# Microcontroleur.net
KiCad netlist of a schematic drawn in Altium Designer
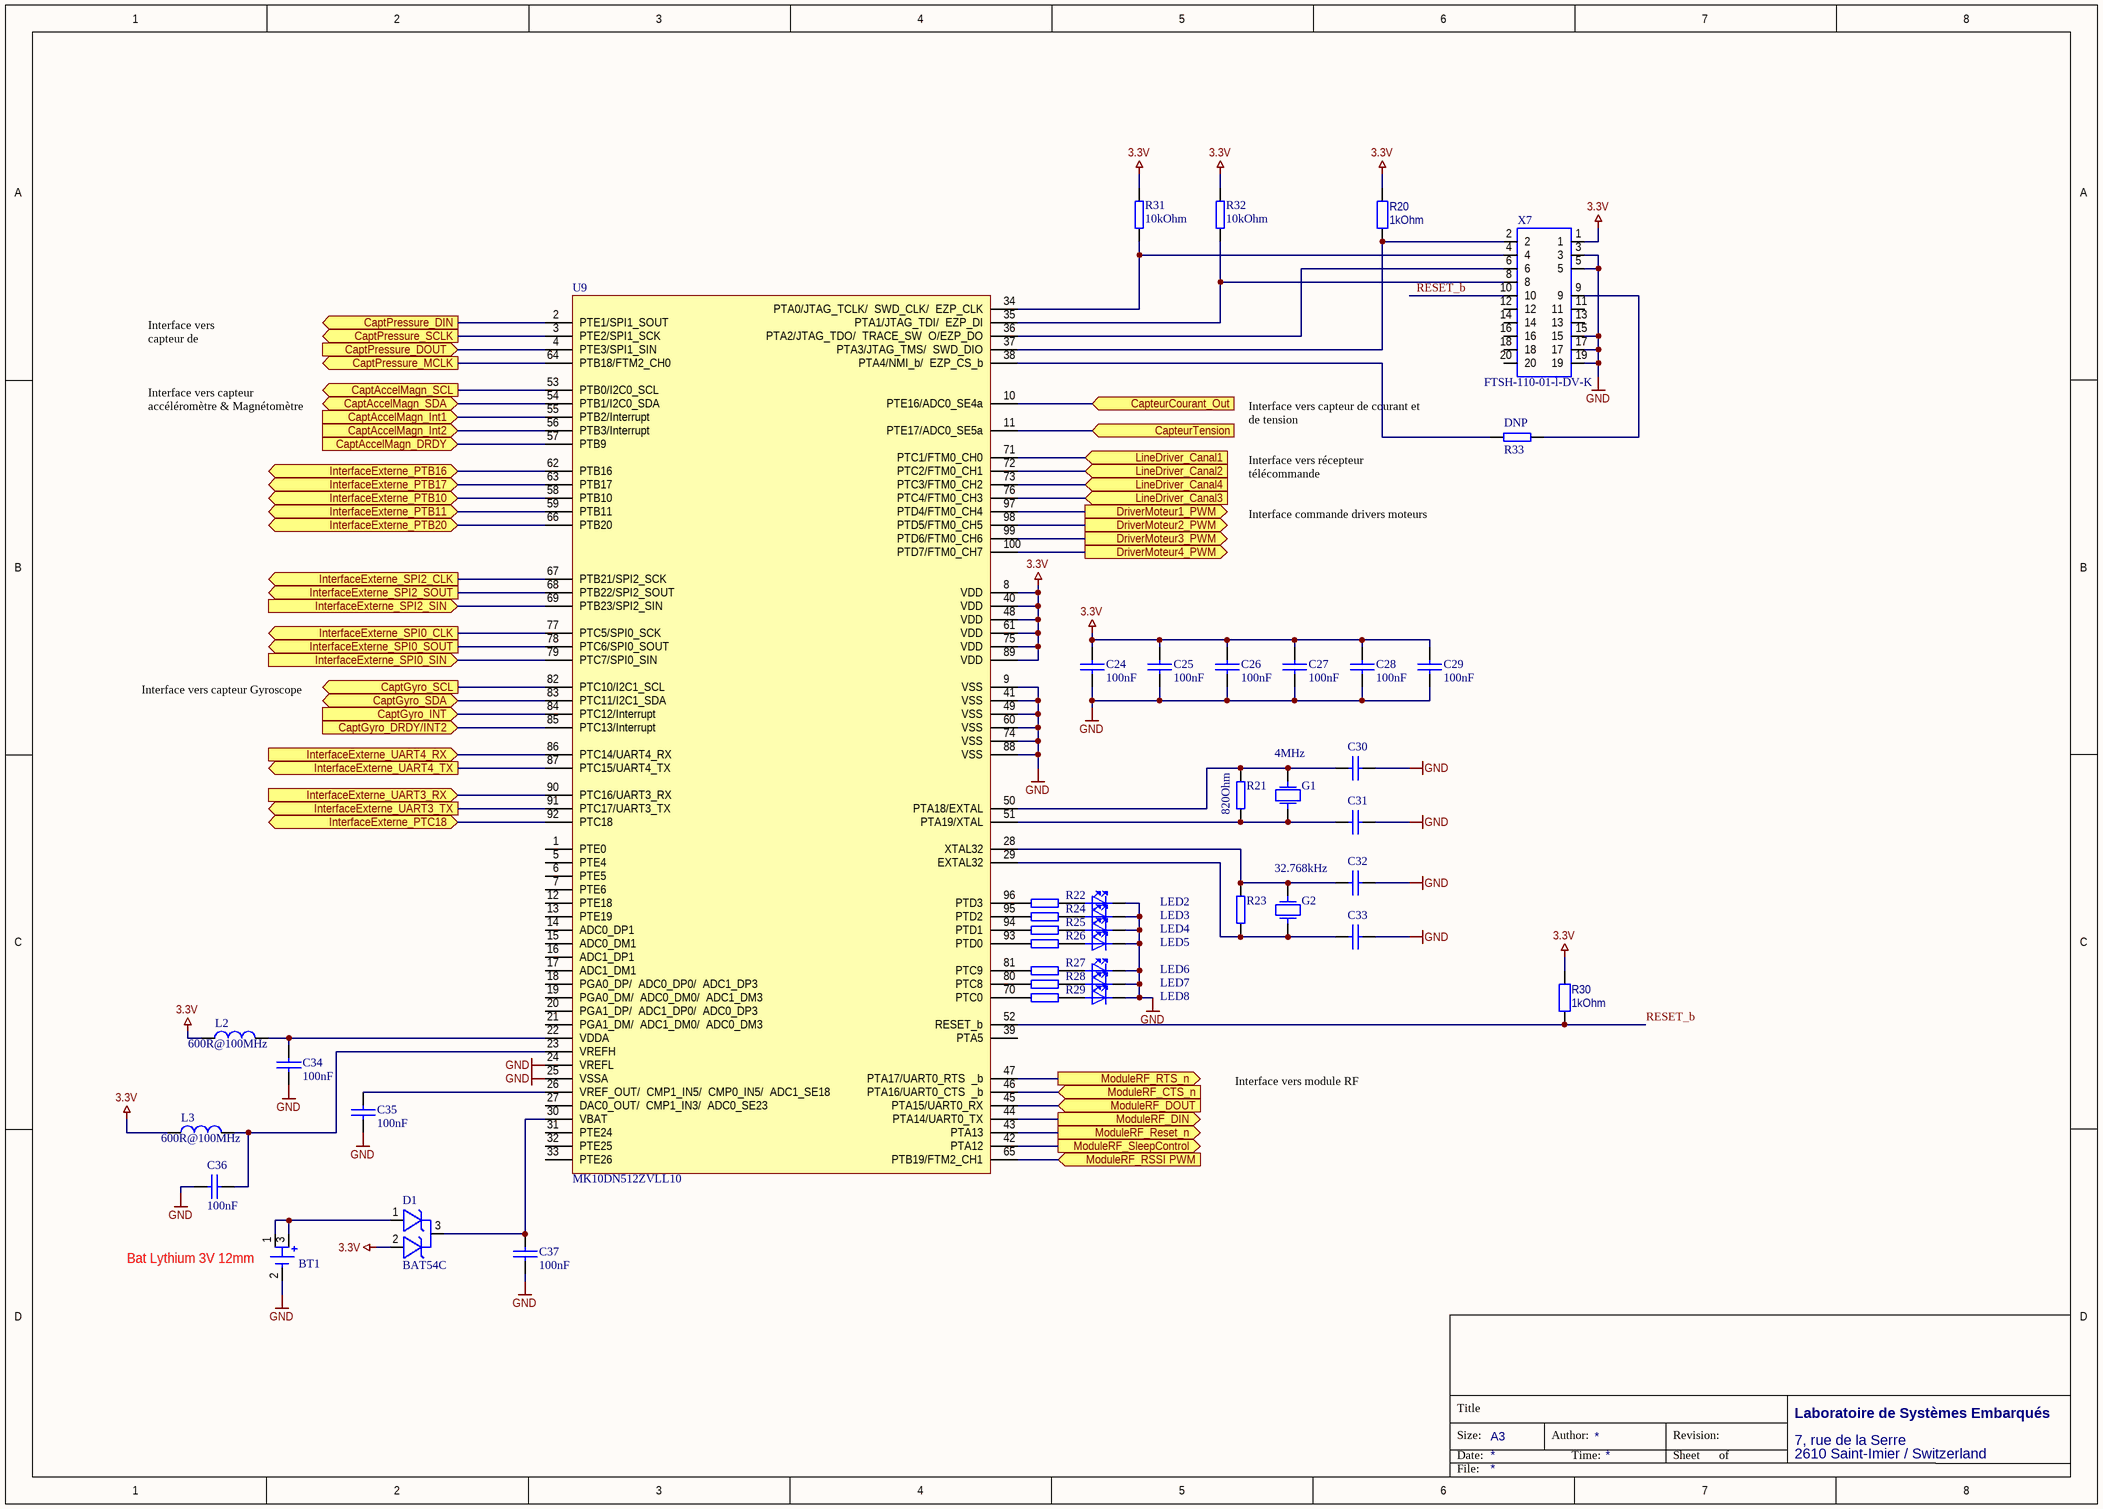
[diagram p0: Microcontroleur.SchDoc]

(export (version "E")
  (design (tool "Eeschema 10.0.6"))
  (components
    (comp (ref "BT1")
      (value "3000TR")
      (footprint "3000TR")
      (description "HOLDER BATTERY COIN 12MM DIA SMD")
      (fields (field (name "MANUFACTURER") "Keystone Electronics"))
      (libsource (lib "EISI") (part "BAT_1"))
    )
    (comp (ref "C24")
      (value "100nF")
      (footprint "060301")
      (description "CAPA")
      (fields (field (name "Comment") "GRM188R71E104KA01D"))
      (libsource (lib "General-Sch-205") (part "CAPA"))
    )
    (comp (ref "C25")
      (value "100nF")
      (footprint "060301")
      (description "CAPA")
      (fields (field (name "Comment") "GRM188R71E104KA01D"))
      (libsource (lib "General-Sch-205") (part "CAPA"))
    )
    (comp (ref "C26")
      (value "100nF")
      (footprint "060301")
      (description "CAPA")
      (fields (field (name "Comment") "GRM188R71E104KA01D"))
      (libsource (lib "General-Sch-205") (part "CAPA"))
    )
    (comp (ref "C27")
      (value "100nF")
      (footprint "060301")
      (description "CAPA")
      (fields (field (name "Comment") "GRM188R71E104KA01D"))
      (libsource (lib "General-Sch-205") (part "CAPA"))
    )
    (comp (ref "C28")
      (value "100nF")
      (footprint "060301")
      (description "CAPA")
      (fields (field (name "Comment") "GRM188R71E104KA01D"))
      (libsource (lib "General-Sch-205") (part "CAPA"))
    )
    (comp (ref "C29")
      (value "100nF")
      (footprint "060301")
      (description "CAPA")
      (fields (field (name "Comment") "GRM188R71E104KA01D"))
      (libsource (lib "General-Sch-205") (part "CAPA"))
    )
    (comp (ref "C30")
      (value "GQM2195C1H200JB01D")
      (footprint "060301")
      (description "CAPA")
      (libsource (lib "General-Sch-205") (part "CAPA"))
    )
    (comp (ref "C31")
      (value "GQM2195C1H200JB01D")
      (footprint "080501")
      (description "CAPA")
      (libsource (lib "General-Sch-205") (part "CAPA"))
    )
    (comp (ref "C32")
      (value "GRM21A5C2E120JW01D")
      (footprint "080501")
      (description "CAPA")
      (libsource (lib "General-Sch-205") (part "CAPA"))
    )
    (comp (ref "C33")
      (value "GRM21A5C2E120JW01D")
      (footprint "080501")
      (description "CAPA")
      (libsource (lib "General-Sch-205") (part "CAPA"))
    )
    (comp (ref "C34")
      (value "100nF")
      (footprint "060301")
      (description "CAPA")
      (fields (field (name "Comment") "GRM188R71E104KA01D"))
      (libsource (lib "General-Sch-205") (part "CAPA"))
    )
    (comp (ref "C35")
      (value "100nF")
      (footprint "060301")
      (description "CAPA")
      (fields (field (name "Comment") "GRM188R71E104KA01D"))
      (libsource (lib "General-Sch-205") (part "CAPA"))
    )
    (comp (ref "C36")
      (value "100nF")
      (footprint "060301")
      (description "CAPA")
      (fields (field (name "Comment") "GRM188R71E104KA01D"))
      (libsource (lib "General-Sch-205") (part "CAPA"))
    )
    (comp (ref "C37")
      (value "100nF")
      (footprint "060301")
      (description "CAPA")
      (fields (field (name "Comment") "GRM188R71E104KA01D"))
      (libsource (lib "General-Sch-205") (part "CAPA"))
    )
    (comp (ref "D1")
      (value "BAT54C")
      (footprint "SOT2301")
      (description "DIODE SCHTTKY CC 200MA 30V SOT23")
      (fields (field (name "MANUFACTURER") "Comchip Technology"))
      (libsource (lib "EISI") (part "BAT54C"))
    )
    (comp (ref "G1")
      (value "4MHz")
      (footprint "Crystal")
      (fields (field (name "Comment") "ECS-40-20-5PX-TR"))
      (libsource (lib "General-Sch-205") (part "CRYSTAL"))
    )
    (comp (ref "G2")
      (value "32.768kHz")
      (footprint "Crystal2")
      (fields (field (name "Comment") "ECS-.327-12.5-38"))
      (libsource (lib "") (part "CRYSTAL_1"))
    )
    (comp (ref "L2")
      (value "600R@100MHz")
      (footprint "080501")
      (description "FERRITE CHIP 600 OHM 200MA 0805")
      (fields (field (name "MANUFACTURER") "Murata Electronics") (field (name "Comment") "BLM21AG601SN1D"))
      (libsource (lib "EISI") (part "Ferrite Bead"))
    )
    (comp (ref "L3")
      (value "600R@100MHz")
      (footprint "080501")
      (description "FERRITE CHIP 600 OHM 200MA 0805")
      (fields (field (name "MANUFACTURER") "Murata Electronics") (field (name "Comment") "BLM21AG601SN1D"))
      (libsource (lib "EISI") (part "Ferrite Bead"))
    )
    (comp (ref "LED2")
      (value "LG L29K-G2J1-24-Z")
      (footprint "060301_led")
      (libsource (lib "Schlib1") (part "LED"))
    )
    (comp (ref "LED3")
      (value "LG L29K-G2J1-24-Z")
      (footprint "060301_led")
      (libsource (lib "Schlib1") (part "LED"))
    )
    (comp (ref "LED4")
      (value "LG L29K-G2J1-24-Z")
      (footprint "060301_led")
      (libsource (lib "Schlib1") (part "LED"))
    )
    (comp (ref "LED5")
      (value "LG L29K-G2J1-24-Z")
      (footprint "060301_led")
      (libsource (lib "Schlib1") (part "LED"))
    )
    (comp (ref "LED6")
      (value "LG L29K-G2J1-24-Z")
      (footprint "060301_led")
      (libsource (lib "Schlib1") (part "LED"))
    )
    (comp (ref "LED7")
      (value "LG L29K-G2J1-24-Z")
      (footprint "060301_led")
      (libsource (lib "Schlib1") (part "LED"))
    )
    (comp (ref "LED8")
      (value "LG L29K-G2J1-24-Z")
      (footprint "060301_led")
      (libsource (lib "Schlib1") (part "LED"))
    )
    (comp (ref "R20")
      (value "1kOhm")
      (footprint "060301")
      (description "RES 1.00K OHM 1/10W 1% 0603 SMD")
      (fields (field (name "MANUFACTURER") "Yageo") (field (name "Comment") "RC0603FR-071KL"))
      (libsource (lib "EISI") (part "RES"))
    )
    (comp (ref "R21")
      (value "820Ohm")
      (footprint "080501")
      (fields (field (name "Comment") "RMCF0805JT820R"))
      (libsource (lib "General-Sch-205") (part "RES"))
    )
    (comp (ref "R22")
      (value "RMCF0805JT820R")
      (footprint "080501")
      (libsource (lib "General-Sch-205") (part "RES"))
    )
    (comp (ref "R23")
      (value "ERJ-6GEYJ103V")
      (footprint "080501")
      (libsource (lib "General-Sch-205") (part "RES"))
    )
    (comp (ref "R24")
      (value "RMCF0805JT820R")
      (footprint "080501")
      (libsource (lib "General-Sch-205") (part "RES"))
    )
    (comp (ref "R25")
      (value "RMCF0805JT820R")
      (footprint "080501")
      (libsource (lib "General-Sch-205") (part "RES"))
    )
    (comp (ref "R26")
      (value "RMCF0805JT820R")
      (footprint "080501")
      (libsource (lib "General-Sch-205") (part "RES"))
    )
    (comp (ref "R27")
      (value "RMCF0805JT820R")
      (footprint "080501")
      (libsource (lib "General-Sch-205") (part "RES"))
    )
    (comp (ref "R28")
      (value "RMCF0805JT820R")
      (footprint "080501")
      (libsource (lib "General-Sch-205") (part "RES"))
    )
    (comp (ref "R29")
      (value "RMCF0805JT820R")
      (footprint "080501")
      (libsource (lib "General-Sch-205") (part "RES"))
    )
    (comp (ref "R30")
      (value "1kOhm")
      (footprint "060301")
      (description "RES 1.00K OHM 1/10W 1% 0603 SMD")
      (fields (field (name "MANUFACTURER") "Yageo") (field (name "Comment") "RC0603FR-071KL"))
      (libsource (lib "EISI") (part "RES"))
    )
    (comp (ref "R31")
      (value "10kOhm")
      (footprint "080501")
      (fields (field (name "Comment") "ERJ-6GEYJ103V"))
      (libsource (lib "General-Sch-205") (part "RES"))
    )
    (comp (ref "R32")
      (value "10kOhm")
      (footprint "080501")
      (fields (field (name "Comment") "ERJ-6GEYJ103V"))
      (libsource (lib "General-Sch-205") (part "RES"))
    )
    (comp (ref "R33")
      (value "DNP")
      (footprint "080501")
      (fields (field (name "Comment") "RMCF0805JT820R"))
      (libsource (lib "General-Sch-205") (part "RES"))
    )
    (comp (ref "U9")
      (value "MK10DN512ZVLL10")
      (footprint "QFP100-1")
      (libsource (lib "Schlib1") (part "MK10DN512ZVLL10"))
    )
    (comp (ref "X7")
      (value "FTSH-110-01-l-DV-K")
      (footprint "FTSH-110-01-X-DV-EJ")
      (description "CONN UNSHROUDED HDR 20POS .05\"")
      (fields (field (name "MANUFACTURER") "Samtec Inc"))
      (libsource (lib "EISI") (part "CON20_JTAG"))
    )
  )
  (nets
    (net (code "1") (name "/CaptAccelMagn_DRDY") (class "Default")
      (node (ref "U9") (pin "57") (pinfunction "PTB9_57") (pintype "passive"))
    )
    (net (code "2") (name "/CaptAccelMagn_Int1") (class "Default")
      (node (ref "U9") (pin "55") (pinfunction "PTB2/Interrupt_55") (pintype "passive"))
    )
    (net (code "3") (name "/CaptAccelMagn_Int2") (class "Default")
      (node (ref "U9") (pin "56") (pinfunction "PTB3/Interrupt_56") (pintype "passive"))
    )
    (net (code "4") (name "/CaptAccelMagn_SCL") (class "Default")
      (node (ref "U9") (pin "53") (pinfunction "PTB0/I2C0_SCL_53") (pintype "passive"))
    )
    (net (code "5") (name "/CaptAccelMagn_SDA") (class "Default")
      (node (ref "U9") (pin "54") (pinfunction "PTB1/I2C0_SDA_54") (pintype "passive"))
    )
    (net (code "6") (name "/CaptGyro_DRDY{slash}INT2") (class "Default")
      (node (ref "U9") (pin "85") (pinfunction "PTC13/Interrupt_85") (pintype "passive"))
    )
    (net (code "7") (name "/CaptGyro_INT") (class "Default")
      (node (ref "U9") (pin "84") (pinfunction "PTC12/Interrupt_84") (pintype "passive"))
    )
    (net (code "8") (name "/CaptGyro_SCL") (class "Default")
      (node (ref "U9") (pin "82") (pinfunction "PTC10/I2C1_SCL_82") (pintype "passive"))
    )
    (net (code "9") (name "/CaptGyro_SDA") (class "Default")
      (node (ref "U9") (pin "83") (pinfunction "PTC11/I2C1_SDA_83") (pintype "passive"))
    )
    (net (code "10") (name "/CaptPressure_DIN") (class "Default")
      (node (ref "U9") (pin "2") (pinfunction "PTE1/SPI1_SOUT_2") (pintype "passive"))
    )
    (net (code "11") (name "/CaptPressure_DOUT") (class "Default")
      (node (ref "U9") (pin "4") (pinfunction "PTE3/SPI1_SIN_4") (pintype "passive"))
    )
    (net (code "12") (name "/CaptPressure_MCLK") (class "Default")
      (node (ref "U9") (pin "64") (pinfunction "PTB18/FTM2_CH0_64") (pintype "passive"))
    )
    (net (code "13") (name "/CaptPressure_SCLK") (class "Default")
      (node (ref "U9") (pin "3") (pinfunction "PTE2/SPI1_SCK_3") (pintype "passive"))
    )
    (net (code "14") (name "/CapteurCourant_Out") (class "Default")
      (node (ref "U9") (pin "10") (pinfunction "PTE16/ADC0_SE4a_10") (pintype "passive"))
    )
    (net (code "15") (name "/CapteurTension") (class "Default")
      (node (ref "U9") (pin "11") (pinfunction "PTE17/ADC0_SE5a_11") (pintype "passive"))
    )
    (net (code "16") (name "/DriverMoteur1_PWM") (class "Default")
      (node (ref "U9") (pin "97") (pinfunction "PTD4/FTM0_CH4_97") (pintype "passive"))
    )
    (net (code "17") (name "/DriverMoteur2_PWM") (class "Default")
      (node (ref "U9") (pin "98") (pinfunction "PTD5/FTM0_CH5_98") (pintype "passive"))
    )
    (net (code "18") (name "/DriverMoteur3_PWM") (class "Default")
      (node (ref "U9") (pin "99") (pinfunction "PTD6/FTM0_CH6_99") (pintype "passive"))
    )
    (net (code "19") (name "/DriverMoteur4_PWM") (class "Default")
      (node (ref "U9") (pin "100") (pinfunction "PTD7/FTM0_CH7_100") (pintype "passive"))
    )
    (net (code "20") (name "/InterfaceExterne_PTB10") (class "Default")
      (node (ref "U9") (pin "58") (pinfunction "PTB10_58") (pintype "passive"))
    )
    (net (code "21") (name "/InterfaceExterne_PTB11") (class "Default")
      (node (ref "U9") (pin "59") (pinfunction "PTB11_59") (pintype "passive"))
    )
    (net (code "22") (name "/InterfaceExterne_PTB16") (class "Default")
      (node (ref "U9") (pin "62") (pinfunction "PTB16_62") (pintype "passive"))
    )
    (net (code "23") (name "/InterfaceExterne_PTB17") (class "Default")
      (node (ref "U9") (pin "63") (pinfunction "PTB17_63") (pintype "passive"))
    )
    (net (code "24") (name "/InterfaceExterne_PTB20") (class "Default")
      (node (ref "U9") (pin "66") (pinfunction "PTB20_66") (pintype "passive"))
    )
    (net (code "25") (name "/InterfaceExterne_PTC18") (class "Default")
      (node (ref "U9") (pin "92") (pinfunction "PTC18_92") (pintype "passive"))
    )
    (net (code "26") (name "/InterfaceExterne_SPI0_CLK") (class "Default")
      (node (ref "U9") (pin "77") (pinfunction "PTC5/SPI0_SCK_77") (pintype "passive"))
    )
    (net (code "27") (name "/InterfaceExterne_SPI0_SIN") (class "Default")
      (node (ref "U9") (pin "79") (pinfunction "PTC7/SPI0_SIN_79") (pintype "passive"))
    )
    (net (code "28") (name "/InterfaceExterne_SPI0_SOUT") (class "Default")
      (node (ref "U9") (pin "78") (pinfunction "PTC6/SPI0_SOUT_78") (pintype "passive"))
    )
    (net (code "29") (name "/InterfaceExterne_SPI2_CLK") (class "Default")
      (node (ref "U9") (pin "67") (pinfunction "PTB21/SPI2_SCK_67") (pintype "passive"))
    )
    (net (code "30") (name "/InterfaceExterne_SPI2_SIN") (class "Default")
      (node (ref "U9") (pin "69") (pinfunction "PTB23/SPI2_SIN_69") (pintype "passive"))
    )
    (net (code "31") (name "/InterfaceExterne_SPI2_SOUT") (class "Default")
      (node (ref "U9") (pin "68") (pinfunction "PTB22/SPI2_SOUT_68") (pintype "passive"))
    )
    (net (code "32") (name "/InterfaceExterne_UART3_RX") (class "Default")
      (node (ref "U9") (pin "90") (pinfunction "PTC16/UART3_RX_90") (pintype "passive"))
    )
    (net (code "33") (name "/InterfaceExterne_UART3_TX") (class "Default")
      (node (ref "U9") (pin "91") (pinfunction "PTC17/UART3_TX_91") (pintype "passive"))
    )
    (net (code "34") (name "/InterfaceExterne_UART4_RX") (class "Default")
      (node (ref "U9") (pin "86") (pinfunction "PTC14/UART4_RX_86") (pintype "passive"))
    )
    (net (code "35") (name "/InterfaceExterne_UART4_TX") (class "Default")
      (node (ref "U9") (pin "87") (pinfunction "PTC15/UART4_TX_87") (pintype "passive"))
    )
    (net (code "36") (name "/LineDriver_Canal1") (class "Default")
      (node (ref "U9") (pin "71") (pinfunction "PTC1/FTM0_CH0_71") (pintype "passive"))
    )
    (net (code "37") (name "/LineDriver_Canal2") (class "Default")
      (node (ref "U9") (pin "72") (pinfunction "PTC2/FTM0_CH1_72") (pintype "passive"))
    )
    (net (code "38") (name "/LineDriver_Canal3") (class "Default")
      (node (ref "U9") (pin "76") (pinfunction "PTC4/FTM0_CH3_76") (pintype "passive"))
    )
    (net (code "39") (name "/LineDriver_Canal4") (class "Default")
      (node (ref "U9") (pin "73") (pinfunction "PTC3/FTM0_CH2_73") (pintype "passive"))
    )
    (net (code "40") (name "/ModuleRF_CTS_n") (class "Default")
      (node (ref "U9") (pin "46") (pinfunction "PTA16/UART0_CTS___b_46") (pintype "passive"))
    )
    (net (code "41") (name "/ModuleRF_DIN") (class "Default")
      (node (ref "U9") (pin "44") (pinfunction "PTA14/UART0_TX_44") (pintype "passive"))
    )
    (net (code "42") (name "/ModuleRF_DOUT") (class "Default")
      (node (ref "U9") (pin "45") (pinfunction "PTA15/UART0_RX_45") (pintype "passive"))
    )
    (net (code "43") (name "/ModuleRF_RSSI PWM") (class "Default")
      (node (ref "U9") (pin "65") (pinfunction "PTB19/FTM2_CH1_65") (pintype "passive"))
    )
    (net (code "44") (name "/ModuleRF_RTS_n") (class "Default")
      (node (ref "U9") (pin "47") (pinfunction "PTA17/UART0_RTS___b_47") (pintype "passive"))
    )
    (net (code "45") (name "/ModuleRF_Reset_n") (class "Default")
      (node (ref "U9") (pin "43") (pinfunction "PTA13_43") (pintype "passive"))
    )
    (net (code "46") (name "/ModuleRF_SleepControl") (class "Default")
      (node (ref "U9") (pin "42") (pinfunction "PTA12_42") (pintype "passive"))
    )
    (net (code "47") (name "/RESET_b") (class "Default")
      (node (ref "R30") (pin "2") (pinfunction "2_2") (pintype "passive"))
      (node (ref "U9") (pin "52") (pinfunction "RESET_b_52") (pintype "passive"))
      (node (ref "X7") (pin "10") (pinfunction "10_10") (pintype "passive"))
    )
    (net (code "48") (name "3.3V") (class "Default")
      (node (ref "C24") (pin "1") (pintype "passive"))
      (node (ref "C25") (pin "1") (pintype "passive"))
      (node (ref "C26") (pin "1") (pintype "passive"))
      (node (ref "C27") (pin "1") (pintype "passive"))
      (node (ref "C28") (pin "1") (pintype "passive"))
      (node (ref "C29") (pin "1") (pintype "passive"))
      (node (ref "D1") (pin "2") (pinfunction "C2_2") (pintype "passive"))
      (node (ref "L2") (pin "1") (pinfunction "1_1") (pintype "passive"))
      (node (ref "L3") (pin "1") (pinfunction "1_1") (pintype "passive"))
      (node (ref "R20") (pin "1") (pinfunction "1_1") (pintype "passive"))
      (node (ref "R30") (pin "1") (pinfunction "1_1") (pintype "passive"))
      (node (ref "R31") (pin "2") (pintype "passive"))
      (node (ref "R32") (pin "2") (pintype "passive"))
      (node (ref "U9") (pin "40") (pinfunction "VDD_40") (pintype "passive"))
      (node (ref "U9") (pin "48") (pinfunction "VDD_48") (pintype "passive"))
      (node (ref "U9") (pin "61") (pinfunction "VDD_61") (pintype "passive"))
      (node (ref "U9") (pin "75") (pinfunction "VDD_75") (pintype "passive"))
      (node (ref "U9") (pin "8") (pinfunction "VDD_8") (pintype "passive"))
      (node (ref "U9") (pin "89") (pinfunction "VDD_89") (pintype "passive"))
      (node (ref "X7") (pin "1") (pinfunction "1_1") (pintype "passive"))
    )
    (net (code "49") (name "GND") (class "Default")
      (node (ref "BT1") (pin "2") (pinfunction "C_2") (pintype "passive"))
      (node (ref "C24") (pin "2") (pintype "passive"))
      (node (ref "C25") (pin "2") (pintype "passive"))
      (node (ref "C26") (pin "2") (pintype "passive"))
      (node (ref "C27") (pin "2") (pintype "passive"))
      (node (ref "C28") (pin "2") (pintype "passive"))
      (node (ref "C29") (pin "2") (pintype "passive"))
      (node (ref "C30") (pin "2") (pintype "passive"))
      (node (ref "C31") (pin "2") (pintype "passive"))
      (node (ref "C32") (pin "2") (pintype "passive"))
      (node (ref "C33") (pin "2") (pintype "passive"))
      (node (ref "C34") (pin "2") (pintype "passive"))
      (node (ref "C35") (pin "1") (pintype "passive"))
      (node (ref "C36") (pin "1") (pintype "passive"))
      (node (ref "C37") (pin "1") (pintype "passive"))
      (node (ref "LED2") (pin "2") (pinfunction "CATHODE_2") (pintype "passive"))
      (node (ref "LED3") (pin "2") (pinfunction "CATHODE_2") (pintype "passive"))
      (node (ref "LED4") (pin "2") (pinfunction "CATHODE_2") (pintype "passive"))
      (node (ref "LED5") (pin "2") (pinfunction "CATHODE_2") (pintype "passive"))
      (node (ref "LED6") (pin "2") (pinfunction "CATHODE_2") (pintype "passive"))
      (node (ref "LED7") (pin "2") (pinfunction "CATHODE_2") (pintype "passive"))
      (node (ref "LED8") (pin "2") (pinfunction "CATHODE_2") (pintype "passive"))
      (node (ref "U9") (pin "24") (pinfunction "VREFL_24") (pintype "passive"))
      (node (ref "U9") (pin "25") (pinfunction "VSSA_25") (pintype "passive"))
      (node (ref "U9") (pin "41") (pinfunction "VSS_41") (pintype "passive"))
      (node (ref "U9") (pin "49") (pinfunction "VSS_49") (pintype "passive"))
      (node (ref "U9") (pin "60") (pinfunction "VSS_60") (pintype "passive"))
      (node (ref "U9") (pin "74") (pinfunction "VSS_74") (pintype "passive"))
      (node (ref "U9") (pin "88") (pinfunction "VSS_88") (pintype "passive"))
      (node (ref "U9") (pin "9") (pinfunction "VSS_9") (pintype "passive"))
      (node (ref "X7") (pin "15") (pinfunction "15_15") (pintype "passive"))
      (node (ref "X7") (pin "17") (pinfunction "17_17") (pintype "passive"))
      (node (ref "X7") (pin "19") (pinfunction "19_19") (pintype "passive"))
      (node (ref "X7") (pin "3") (pinfunction "3_3") (pintype "passive"))
      (node (ref "X7") (pin "5") (pinfunction "5_5") (pintype "passive"))
    )
    (net (code "50") (name "Net-(BT1-A1)") (class "Default")
      (node (ref "BT1") (pin "1") (pinfunction "A1_1") (pintype "passive"))
      (node (ref "BT1") (pin "3") (pinfunction "A2_3") (pintype "passive"))
      (node (ref "D1") (pin "1") (pinfunction "C1_1") (pintype "passive"))
    )
    (net (code "51") (name "Net-(D1-Anode)") (class "Default")
      (node (ref "C37") (pin "2") (pintype "passive"))
      (node (ref "D1") (pin "3") (pinfunction "Anode_3") (pintype "passive"))
      (node (ref "U9") (pin "30") (pinfunction "VBAT_30") (pintype "passive"))
    )
    (net (code "52") (name "Net-(LED2-ANODE)") (class "Default")
      (node (ref "LED2") (pin "1") (pinfunction "ANODE_1") (pintype "passive"))
      (node (ref "R24") (pin "2") (pintype "passive"))
    )
    (net (code "53") (name "Net-(LED3-ANODE)") (class "Default")
      (node (ref "LED3") (pin "1") (pinfunction "ANODE_1") (pintype "passive"))
      (node (ref "R22") (pin "2") (pintype "passive"))
    )
    (net (code "54") (name "Net-(LED4-ANODE)") (class "Default")
      (node (ref "LED4") (pin "1") (pinfunction "ANODE_1") (pintype "passive"))
      (node (ref "R25") (pin "2") (pintype "passive"))
    )
    (net (code "55") (name "Net-(LED5-ANODE)") (class "Default")
      (node (ref "LED5") (pin "1") (pinfunction "ANODE_1") (pintype "passive"))
      (node (ref "R26") (pin "2") (pintype "passive"))
    )
    (net (code "56") (name "Net-(LED6-ANODE)") (class "Default")
      (node (ref "LED6") (pin "1") (pinfunction "ANODE_1") (pintype "passive"))
      (node (ref "R27") (pin "2") (pintype "passive"))
    )
    (net (code "57") (name "Net-(LED7-ANODE)") (class "Default")
      (node (ref "LED7") (pin "1") (pinfunction "ANODE_1") (pintype "passive"))
      (node (ref "R28") (pin "2") (pintype "passive"))
    )
    (net (code "58") (name "Net-(LED8-ANODE)") (class "Default")
      (node (ref "LED8") (pin "1") (pinfunction "ANODE_1") (pintype "passive"))
      (node (ref "R29") (pin "2") (pintype "passive"))
    )
    (net (code "59") (name "Net-(R33-Pad1)") (class "Default")
      (node (ref "R33") (pin "1") (pintype "passive"))
      (node (ref "X7") (pin "9") (pinfunction "9_9") (pintype "passive"))
    )
    (net (code "60") (name "Net-(U9-EXTAL32)") (class "Default")
      (node (ref "C33") (pin "1") (pintype "passive"))
      (node (ref "G2") (pin "1") (pintype "passive"))
      (node (ref "R23") (pin "1") (pintype "passive"))
      (node (ref "U9") (pin "29") (pinfunction "EXTAL32_29") (pintype "passive"))
    )
    (net (code "61") (name "Net-(U9-PTA0{slash}JTAG_TCLK{slash}__SWD_CLK{slash}__EZP_CLK)") (class "Default")
      (node (ref "R31") (pin "1") (pintype "passive"))
      (node (ref "U9") (pin "34") (pinfunction "PTA0/JTAG_TCLK/__SWD_CLK/__EZP_CLK_34") (pintype "passive"))
      (node (ref "X7") (pin "4") (pinfunction "4_4") (pintype "passive"))
    )
    (net (code "62") (name "Net-(U9-PTA1{slash}JTAG_TDI{slash}__EZP_DI)") (class "Default")
      (node (ref "R32") (pin "1") (pintype "passive"))
      (node (ref "U9") (pin "35") (pinfunction "PTA1/JTAG_TDI/__EZP_DI_35") (pintype "passive"))
      (node (ref "X7") (pin "8") (pinfunction "8_8") (pintype "passive"))
    )
    (net (code "63") (name "Net-(U9-PTA2{slash}JTAG_TDO{slash}__TRACE_SW__O{slash}EZP_DO)") (class "Default")
      (node (ref "U9") (pin "36") (pinfunction "PTA2/JTAG_TDO/__TRACE_SW__O/EZP_DO_36") (pintype "passive"))
      (node (ref "X7") (pin "6") (pinfunction "6_6") (pintype "passive"))
    )
    (net (code "64") (name "Net-(U9-PTA3{slash}JTAG_TMS{slash}__SWD_DIO)") (class "Default")
      (node (ref "R20") (pin "2") (pinfunction "2_2") (pintype "passive"))
      (node (ref "U9") (pin "37") (pinfunction "PTA3/JTAG_TMS/__SWD_DIO_37") (pintype "passive"))
      (node (ref "X7") (pin "2") (pinfunction "2_2") (pintype "passive"))
    )
    (net (code "65") (name "Net-(U9-PTA4{slash}NMI_b{slash}__EZP_CS_b)") (class "Default")
      (node (ref "R33") (pin "2") (pintype "passive"))
      (node (ref "U9") (pin "38") (pinfunction "PTA4/NMI_b/__EZP_CS_b_38") (pintype "passive"))
    )
    (net (code "66") (name "Net-(U9-PTA18{slash}EXTAL)") (class "Default")
      (node (ref "C30") (pin "1") (pintype "passive"))
      (node (ref "G1") (pin "1") (pintype "passive"))
      (node (ref "R21") (pin "2") (pintype "passive"))
      (node (ref "U9") (pin "50") (pinfunction "PTA18/EXTAL_50") (pintype "passive"))
    )
    (net (code "67") (name "Net-(U9-PTA19{slash}XTAL)") (class "Default")
      (node (ref "C31") (pin "1") (pintype "passive"))
      (node (ref "G1") (pin "2") (pinfunction "2_2") (pintype "passive"))
      (node (ref "R21") (pin "1") (pintype "passive"))
      (node (ref "U9") (pin "51") (pinfunction "PTA19/XTAL_51") (pintype "passive"))
    )
    (net (code "68") (name "Net-(U9-PTC0)") (class "Default")
      (node (ref "R29") (pin "1") (pintype "passive"))
      (node (ref "U9") (pin "70") (pinfunction "PTC0_70") (pintype "passive"))
    )
    (net (code "69") (name "Net-(U9-PTC8)") (class "Default")
      (node (ref "R28") (pin "1") (pintype "passive"))
      (node (ref "U9") (pin "80") (pinfunction "PTC8_80") (pintype "passive"))
    )
    (net (code "70") (name "Net-(U9-PTC9)") (class "Default")
      (node (ref "R27") (pin "1") (pintype "passive"))
      (node (ref "U9") (pin "81") (pinfunction "PTC9_81") (pintype "passive"))
    )
    (net (code "71") (name "Net-(U9-PTD0)") (class "Default")
      (node (ref "R26") (pin "1") (pintype "passive"))
      (node (ref "U9") (pin "93") (pinfunction "PTD0_93") (pintype "passive"))
    )
    (net (code "72") (name "Net-(U9-PTD1)") (class "Default")
      (node (ref "R25") (pin "1") (pintype "passive"))
      (node (ref "U9") (pin "94") (pinfunction "PTD1_94") (pintype "passive"))
    )
    (net (code "73") (name "Net-(U9-PTD2)") (class "Default")
      (node (ref "R24") (pin "1") (pintype "passive"))
      (node (ref "U9") (pin "95") (pinfunction "PTD2_95") (pintype "passive"))
    )
    (net (code "74") (name "Net-(U9-PTD3)") (class "Default")
      (node (ref "R22") (pin "1") (pintype "passive"))
      (node (ref "U9") (pin "96") (pinfunction "PTD3_96") (pintype "passive"))
    )
    (net (code "75") (name "Net-(U9-VDDA)") (class "Default")
      (node (ref "C34") (pin "1") (pintype "passive"))
      (node (ref "L2") (pin "2") (pinfunction "2_2") (pintype "passive"))
      (node (ref "U9") (pin "22") (pinfunction "VDDA_22") (pintype "passive"))
    )
    (net (code "76") (name "Net-(U9-VREFH)") (class "Default")
      (node (ref "C36") (pin "2") (pintype "passive"))
      (node (ref "L3") (pin "2") (pinfunction "2_2") (pintype "passive"))
      (node (ref "U9") (pin "23") (pinfunction "VREFH_23") (pintype "passive"))
    )
    (net (code "77") (name "Net-(U9-VREF_OUT{slash}__CMP1_IN5{slash}__CMP0_IN5{slash}__ADC1_SE18)") (class "Default")
      (node (ref "C35") (pin "2") (pintype "passive"))
      (node (ref "U9") (pin "26") (pinfunction "VREF_OUT/__CMP1_IN5/__CMP0_IN5/__ADC1_SE18_26") (pintype "passive"))
    )
    (net (code "78") (name "Net-(U9-XTAL32)") (class "Default")
      (node (ref "C32") (pin "1") (pintype "passive"))
      (node (ref "G2") (pin "2") (pintype "passive"))
      (node (ref "R23") (pin "2") (pintype "passive"))
      (node (ref "U9") (pin "28") (pinfunction "XTAL32_28") (pintype "passive"))
    )
    (net (code "79") (name "unconnected-(U9-ADC0_DM1-Pad15)") (class "Default")
      (node (ref "U9") (pin "15") (pinfunction "ADC0_DM1_15") (pintype "passive"))
    )
    (net (code "80") (name "unconnected-(U9-ADC0_DP1-Pad14)") (class "Default")
      (node (ref "U9") (pin "14") (pinfunction "ADC0_DP1_14") (pintype "passive"))
    )
    (net (code "81") (name "unconnected-(U9-ADC1_DM1-Pad17)") (class "Default")
      (node (ref "U9") (pin "17") (pinfunction "ADC1_DM1_17") (pintype "passive"))
    )
    (net (code "82") (name "unconnected-(U9-ADC1_DP1-Pad16)") (class "Default")
      (node (ref "U9") (pin "16") (pinfunction "ADC1_DP1_16") (pintype "passive"))
    )
    (net (code "83") (name "unconnected-(U9-DAC0_OUT{slash}__CMP1_IN3{slash}__ADC0_SE23-Pad27)") (class "Default")
      (node (ref "U9") (pin "27") (pinfunction "DAC0_OUT/__CMP1_IN3/__ADC0_SE23_27") (pintype "passive"))
    )
    (net (code "84") (name "unconnected-(U9-PGA0_DM{slash}__ADC0_DM0{slash}__ADC1_DM3-Pad19)") (class "Default")
      (node (ref "U9") (pin "19") (pinfunction "PGA0_DM/__ADC0_DM0/__ADC1_DM3_19") (pintype "passive"))
    )
    (net (code "85") (name "unconnected-(U9-PGA0_DP{slash}__ADC0_DP0{slash}__ADC1_DP3-Pad18)") (class "Default")
      (node (ref "U9") (pin "18") (pinfunction "PGA0_DP/__ADC0_DP0/__ADC1_DP3_18") (pintype "passive"))
    )
    (net (code "86") (name "unconnected-(U9-PGA1_DM{slash}__ADC1_DM0{slash}__ADC0_DM3-Pad21)") (class "Default")
      (node (ref "U9") (pin "21") (pinfunction "PGA1_DM/__ADC1_DM0/__ADC0_DM3_21") (pintype "passive"))
    )
    (net (code "87") (name "unconnected-(U9-PGA1_DP{slash}__ADC1_DP0{slash}__ADC0_DP3-Pad20)") (class "Default")
      (node (ref "U9") (pin "20") (pinfunction "PGA1_DP/__ADC1_DP0/__ADC0_DP3_20") (pintype "passive"))
    )
    (net (code "88") (name "unconnected-(U9-PTA5-Pad39)") (class "Default")
      (node (ref "U9") (pin "39") (pinfunction "PTA5_39") (pintype "passive"))
    )
    (net (code "89") (name "unconnected-(U9-PTE0-Pad1)") (class "Default")
      (node (ref "U9") (pin "1") (pinfunction "PTE0_1") (pintype "passive"))
    )
    (net (code "90") (name "unconnected-(U9-PTE4-Pad5)") (class "Default")
      (node (ref "U9") (pin "5") (pinfunction "PTE4_5") (pintype "passive"))
    )
    (net (code "91") (name "unconnected-(U9-PTE5-Pad6)") (class "Default")
      (node (ref "U9") (pin "6") (pinfunction "PTE5_6") (pintype "passive"))
    )
    (net (code "92") (name "unconnected-(U9-PTE6-Pad7)") (class "Default")
      (node (ref "U9") (pin "7") (pinfunction "PTE6_7") (pintype "passive"))
    )
    (net (code "93") (name "unconnected-(U9-PTE18-Pad12)") (class "Default")
      (node (ref "U9") (pin "12") (pinfunction "PTE18_12") (pintype "passive"))
    )
    (net (code "94") (name "unconnected-(U9-PTE19-Pad13)") (class "Default")
      (node (ref "U9") (pin "13") (pinfunction "PTE19_13") (pintype "passive"))
    )
    (net (code "95") (name "unconnected-(U9-PTE24-Pad31)") (class "Default")
      (node (ref "U9") (pin "31") (pinfunction "PTE24_31") (pintype "passive"))
    )
    (net (code "96") (name "unconnected-(U9-PTE25-Pad32)") (class "Default")
      (node (ref "U9") (pin "32") (pinfunction "PTE25_32") (pintype "passive"))
    )
    (net (code "97") (name "unconnected-(U9-PTE26-Pad33)") (class "Default")
      (node (ref "U9") (pin "33") (pinfunction "PTE26_33") (pintype "passive"))
    )
    (net (code "98") (name "unconnected-(X7-Pad11)") (class "Default")
      (node (ref "X7") (pin "11") (pinfunction "11_11") (pintype "passive"))
    )
    (net (code "99") (name "unconnected-(X7-Pad12)") (class "Default")
      (node (ref "X7") (pin "12") (pinfunction "12_12") (pintype "passive"))
    )
    (net (code "100") (name "unconnected-(X7-Pad13)") (class "Default")
      (node (ref "X7") (pin "13") (pinfunction "13_13") (pintype "passive"))
    )
    (net (code "101") (name "unconnected-(X7-Pad14)") (class "Default")
      (node (ref "X7") (pin "14") (pinfunction "14_14") (pintype "passive"))
    )
    (net (code "102") (name "unconnected-(X7-Pad16)") (class "Default")
      (node (ref "X7") (pin "16") (pinfunction "16_16") (pintype "passive"))
    )
    (net (code "103") (name "unconnected-(X7-Pad18)") (class "Default")
      (node (ref "X7") (pin "18") (pinfunction "18_18") (pintype "passive"))
    )
    (net (code "104") (name "unconnected-(X7-Pad20)") (class "Default")
      (node (ref "X7") (pin "20") (pinfunction "20_20") (pintype "passive"))
    )
  )
)
